# schema3.net
KiCad netlist of a schematic drawn in Altium Designer
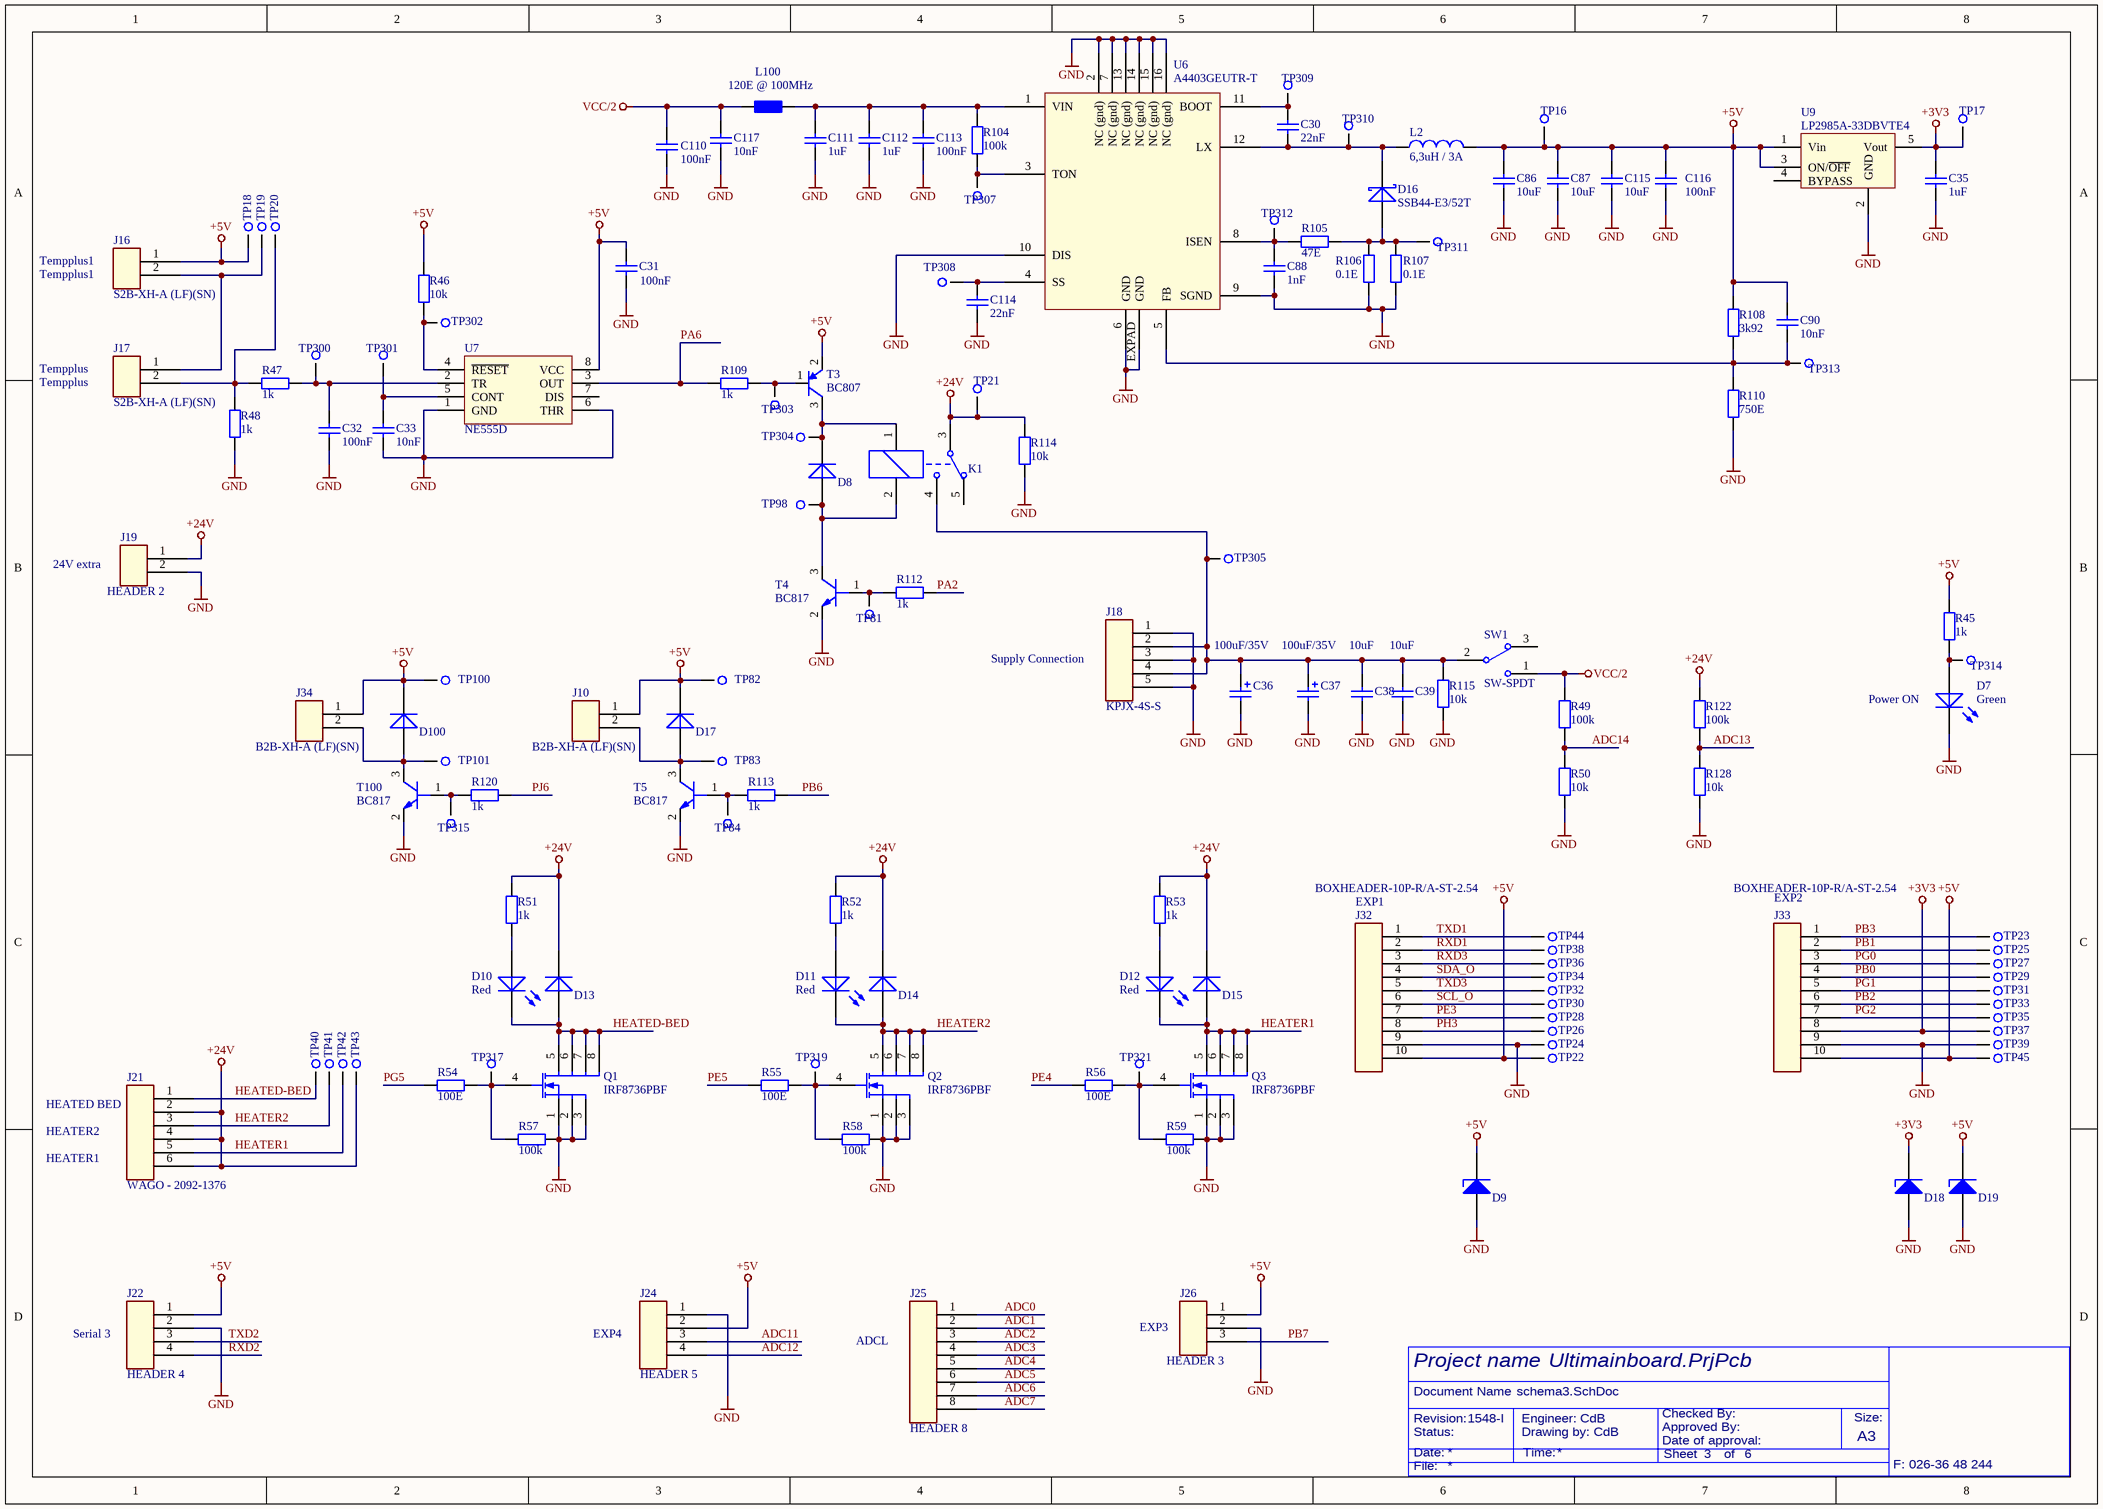
[diagram p0: schema3.SchDoc]

(export (version "E")
  (design (tool "Eeschema 10.0.6"))
  (components
    (comp (ref "C30")
      (value "22nF")
      (footprint "C0603")
      (description "RO X7R 22nF 10% 0603 50V CC0603KRX7R9BB223")
      (libsource (lib "Database_Faber") (part "Capacitor"))
    )
    (comp (ref "C31")
      (value "100nF")
      (footprint "C0603")
      (description "RO X7R 100nF 10% 50V 0603")
      (libsource (lib "Database_Faber") (part "Capacitor"))
    )
    (comp (ref "C32")
      (value "100nF")
      (footprint "C0603")
      (description "RO X7R 100nF 10% 50V 0603")
      (libsource (lib "Database_Faber") (part "Capacitor"))
    )
    (comp (ref "C33")
      (value "10nF")
      (footprint "C0603")
      (description "RO X7R 10nF 10% 50V 0603")
      (libsource (lib "Database_Faber") (part "Capacitor"))
    )
    (comp (ref "C35")
      (value "1uF")
      (footprint "C0603")
      (description "RO X5R 1uF 10% 10V 0603")
      (libsource (lib "Database_Faber") (part "Capacitor"))
    )
    (comp (ref "C36")
      (value "100uF/35V")
      (footprint "ELCO Case D")
      (description "RO ELCO 100uF 20% 35V CASE-D EEEFP PAN")
      (libsource (lib "Database_Faber") (part "Capacitor Polarity"))
    )
    (comp (ref "C37")
      (value "100uF/35V")
      (footprint "ELCO Case D")
      (description "RO ELCO 100uF 20% 35V CASE-D EEEFP PAN")
      (libsource (lib "Database_Faber") (part "Capacitor Polarity"))
    )
    (comp (ref "C38")
      (value "10uF")
      (footprint "C1206")
      (description "RO X5R 10UF 10% 35V 1206")
      (libsource (lib "Database_Faber") (part "Capacitor"))
    )
    (comp (ref "C39")
      (value "10uF")
      (footprint "C1206")
      (description "RO X5R 10UF 10% 35V 1206")
      (libsource (lib "Database_Faber") (part "Capacitor"))
    )
    (comp (ref "C86")
      (value "10uF")
      (footprint "C0805")
      (description "6R3R15X106KV4E - MLCC, 0805, X5R, 6.3V, 10UF")
      (fields (field (name "MFG") "JOHANSON DIELECTRICS"))
      (libsource (lib "Database_Faber") (part "Capacitor"))
    )
    (comp (ref "C87")
      (value "10uF")
      (footprint "C0805")
      (description "6R3R15X106KV4E - MLCC, 0805, X5R, 6.3V, 10UF")
      (fields (field (name "MFG") "JOHANSON DIELECTRICS"))
      (libsource (lib "Database_Faber") (part "Capacitor"))
    )
    (comp (ref "C88")
      (value "1nF")
      (footprint "C0603")
      (description "RO C0G 1nF 5% 50V 0603")
      (libsource (lib "Database_Faber") (part "Capacitor"))
    )
    (comp (ref "C90")
      (value "10nF")
      (footprint "C0603")
      (description "RO X7R 10nF 10% 50V 0603")
      (libsource (lib "Database_Faber") (part "Capacitor"))
    )
    (comp (ref "C110")
      (value "100nF")
      (footprint "Ultimaker:C0603")
      (description "RO X7R 100nF 10% 50V 0603")
      (libsource (lib "Database_Faber") (part "Capacitor"))
    )
    (comp (ref "C111")
      (value "1uF")
      (footprint "Ultimaker:C1206")
      (description "X7R 1uF 10% 50V 1206 GRM31")
      (libsource (lib "Ultimaker") (part "Capacitor_1_1"))
    )
    (comp (ref "C112")
      (value "1uF")
      (footprint "Ultimaker:C1206")
      (description "X7R 1uF 10% 50V 1206 GRM31")
      (libsource (lib "Ultimaker") (part "Capacitor_1_1"))
    )
    (comp (ref "C113")
      (value "100nF")
      (footprint "Ultimaker:C0603")
      (description "RO X7R 100nF 10% 50V 0603")
      (libsource (lib "Database_Faber") (part "Capacitor"))
    )
    (comp (ref "C114")
      (value "22nF")
      (footprint "Ultimaker:C0603")
      (description "RO X7R 22nF 10% 0603 50V CC0603KRX7R9BB223")
      (libsource (lib "Database_Faber") (part "Capacitor"))
    )
    (comp (ref "C115")
      (value "10uF")
      (footprint "Ultimaker:C0805")
      (description "6R3R15X106KV4E - MLCC, 0805, X5R, 6.3V, 10UF")
      (fields (field (name "MFG") "JOHANSON DIELECTRICS"))
      (libsource (lib "Database_Faber") (part "Capacitor"))
    )
    (comp (ref "C116")
      (value "100nF")
      (footprint "Ultimaker:C0603")
      (description "RO X7R 100nF 10% 50V 0603")
      (libsource (lib "Database_Faber") (part "Capacitor"))
    )
    (comp (ref "C117")
      (value "10nF")
      (footprint "Ultimaker:C0603")
      (description "RO X7R 10nF 10% 50V 0603")
      (libsource (lib "Database_Faber") (part "Capacitor"))
    )
    (comp (ref "D7")
      (value "Green")
      (footprint "LED0805-GREEN")
      (description "RO LED GROEN HSMG-C170 0805 AVAGO")
      (fields (field (name "MFG") "AVAGO"))
      (libsource (lib "Database_Faber") (part "LED"))
    )
    (comp (ref "D8")
      (value "S1G")
      (footprint "DO214AC (SMA)")
      (description "RO DIODE S1G DO-214AC")
      (libsource (lib "Database_Faber") (part "Diode"))
    )
    (comp (ref "D9")
      (value "ESD9X5.0ST5G")
      (footprint "SODFL100X40-2N")
      (description "TVS DIODE 5VWM 12.3VC SOD923")
      (fields (field (name "MFG") "ON Semiconductor"))
      (libsource (lib "Olimex interface board") (part "ESD9X5.0ST5G"))
    )
    (comp (ref "D10")
      (value "Red")
      (footprint "LED0805-RED")
      (description "RO LED ROOD HSMH-C170 0805 AVAGO")
      (fields (field (name "MFG") "AVAGO"))
      (libsource (lib "Database_Faber") (part "LED"))
    )
    (comp (ref "D11")
      (value "Red")
      (footprint "LED0805-RED")
      (description "RO LED ROOD HSMH-C170 0805 AVAGO")
      (fields (field (name "MFG") "AVAGO"))
      (libsource (lib "Database_Faber") (part "LED"))
    )
    (comp (ref "D12")
      (value "Red")
      (footprint "LED0805-RED")
      (description "RO LED ROOD HSMH-C170 0805 AVAGO")
      (fields (field (name "MFG") "AVAGO"))
      (libsource (lib "Database_Faber") (part "LED"))
    )
    (comp (ref "D13")
      (value "S1G")
      (footprint "DO214AC (SMA)")
      (description "RO DIODE S1G DO-214AC")
      (libsource (lib "Database_Faber") (part "Diode"))
    )
    (comp (ref "D14")
      (value "S1G")
      (footprint "DO214AC (SMA)")
      (description "RO DIODE S1G DO-214AC")
      (libsource (lib "Database_Faber") (part "Diode"))
    )
    (comp (ref "D15")
      (value "S1G")
      (footprint "DO214AC (SMA)")
      (description "RO DIODE S1G DO-214AC")
      (libsource (lib "Database_Faber") (part "Diode"))
    )
    (comp (ref "D16")
      (value "SSB44-E3/52T")
      (footprint "DO214AA (SMB)")
      (description "RO DIODE SSB44-E3/52T SMB VISHAY")
      (fields (field (name "MFG") "VISHAY"))
      (libsource (lib "Database_Faber") (part "Schottky"))
    )
    (comp (ref "D17")
      (value "S1G")
      (footprint "Ultimaker:DO214AC (SMA)")
      (description "RO DIODE S1G DO-214AC")
      (libsource (lib "") (part "Diode_1"))
    )
    (comp (ref "D18")
      (value "ESD9X3.3ST5G")
      (footprint "SODFL100X40-2N")
      (description "TVS DIODE 3.3VWM 10.4VC SOD923")
      (fields (field (name "MFG") "ON Semiconductor"))
      (libsource (lib "Olimex interface board") (part "ESD9X3.3ST5G"))
    )
    (comp (ref "D19")
      (value "ESD9X5.0ST5G")
      (footprint "SODFL100X40-2N")
      (description "TVS DIODE 5VWM 12.3VC SOD923")
      (fields (field (name "MFG") "ON Semiconductor"))
      (libsource (lib "Olimex interface board") (part "ESD9X5.0ST5G"))
    )
    (comp (ref "D100")
      (value "S1G")
      (footprint "Ultimaker:DO214AC (SMA)")
      (description "RO DIODE S1G DO-214AC")
      (libsource (lib "") (part "Diode_1"))
    )
    (comp (ref "J10")
      (value "B2B-XH-A (LF)(SN)")
      (footprint "B2B-XH-A (LF)(SN)")
      (description "CONN PR 2p B2B-XH-A JST")
      (fields (field (name "MFG") "JST (JAPAN SOLDERLESS TERMINALS)"))
      (libsource (lib "Ultimaker") (part "HEADER 2_3"))
    )
    (comp (ref "J16")
      (value "S2B-XH-A (LF)(SN)")
      (footprint "S2B-XH-A (LF)(SN)")
      (description "RO CONN PR 2p HKS S2B-XH-A (LF)(SN) JST")
      (fields (field (name "MFG") "JST (JAPAN SOLDERLESS TERMINALS)"))
      (libsource (lib "Database_Faber") (part "HEADER 2"))
    )
    (comp (ref "J17")
      (value "S2B-XH-A (LF)(SN)")
      (footprint "S2B-XH-A (LF)(SN)")
      (description "RO CONN PR 2p HKS S2B-XH-A (LF)(SN) JST")
      (fields (field (name "MFG") "JST (JAPAN SOLDERLESS TERMINALS)"))
      (libsource (lib "Database_Faber") (part "HEADER 2"))
    )
    (comp (ref "J18")
      (value "KPJX-4S-S")
      (footprint "KPJX-4S-S")
      (description "RO CONN PR KPJX-4S-S KYCON")
      (fields (field (name "MFG") "KYCON"))
      (libsource (lib "Database_Faber") (part "HEADER 5"))
    )
    (comp (ref "J19")
      (value "HEADER 2")
      (footprint "HEADER-1x2P-ST-2.54")
      (description "HEADER-1x2P-ST-2.54")
      (libsource (lib "Database_Faber") (part "HEADER 2"))
    )
    (comp (ref "J21")
      (value "WAGO - 2092-1376")
      (footprint "Wago connector:WAGO 2092-1376")
      (description "WAGO - 2092-1376 - TERMINAL BLOCK, PCB, R/A, 6WAY, 24-12AWG")
      (fields (field (name "MFG") "Wago"))
      (libsource (lib "Database_Faber") (part "HEADER 6"))
    )
    (comp (ref "J22")
      (value "HEADER 4")
      (footprint "HEADER-1x4P-ST-2.54")
      (description "HEADER-1x4P-ST-2.54")
      (libsource (lib "Database_Faber") (part "HEADER 4"))
    )
    (comp (ref "J24")
      (value "HEADER 5")
      (footprint "HEADER-1x4P-ST-2.54")
      (description "HEADER-1x4P-ST-2.54")
      (libsource (lib "Database_Faber") (part "HEADER 4"))
    )
    (comp (ref "J25")
      (value "HEADER 8")
      (footprint "HEADER-1x8P-ST-2.54")
      (description "HEADER-1x8P-ST-2.54")
      (libsource (lib "Database_Faber") (part "HEADER 8"))
    )
    (comp (ref "J26")
      (value "HEADER 3")
      (footprint "HEADER-1x3P-ST-2.54")
      (description "HEADER-1x3P-ST-2.54")
      (libsource (lib "Database_Faber") (part "HEADER 3"))
    )
    (comp (ref "J32")
      (value "BOXHEADER-10P-R/A-ST-2.54")
      (footprint "BOXHEADER-10P-R/A-ST-2.54")
      (description "RO CONN PR HDR BOX 10p HKS 61201021721 WUERTH")
      (libsource (lib "Database_Faber") (part "HEADER 10"))
    )
    (comp (ref "J33")
      (value "BOXHEADER-10P-R/A-ST-2.54")
      (footprint "BOXHEADER-10P-R/A-ST-2.54")
      (description "RO CONN PR HDR BOX 10p HKS 61201021721 WUERTH")
      (libsource (lib "Database_Faber") (part "HEADER 10"))
    )
    (comp (ref "J34")
      (value "B2B-XH-A (LF)(SN)")
      (footprint "B2B-XH-A (LF)(SN)")
      (description "CONN PR 2p B2B-XH-A JST")
      (fields (field (name "MFG") "JST (JAPAN SOLDERLESS TERMINALS)"))
      (libsource (lib "Ultimaker") (part "HEADER 2_3"))
    )
    (comp (ref "K1")
      (value "Relay-SPDT")
      (footprint "HRS4-S")
      (description "RO REL 5V HRS4-S DC5V MULTICOMP")
      (fields (field (name "MFG") "MULTICOMP"))
      (libsource (lib "Database_Faber") (part "Relay-SPDT"))
    )
    (comp (ref "L2")
      (value "6,3uH / 3A")
      (footprint "NRS6045")
      (description "RO SPOEL 6,3uH 20% NRS6045T 6R3MMGK TAIYO YUDEN")
      (fields (field (name "MFG") "TAIYO YUDEN"))
      (libsource (lib "Database_Faber") (part "Inductor"))
    )
    (comp (ref "L100")
      (value "120E @ 100MHz")
      (footprint "Ultimaker:R0603")
      (description "FERRIET BLM18PG121SN1D 0603 MURATA")
      (fields (field (name "MFG") "Murata"))
      (libsource (lib "Ultimaker") (part "Ferriet Bead 120E"))
    )
    (comp (ref "Q1")
      (value "IRF8736PBF")
      (footprint "SOIC127P600X175-8N (SO8)")
      (description "IRF8736PBF - MOSFET, N SO-8")
      (fields (field (name "MFG") "INTERNATIONAL RECTIFIER"))
      (libsource (lib "Database_Faber") (part "MOSFET-N-SO8"))
    )
    (comp (ref "Q2")
      (value "IRF8736PBF")
      (footprint "SOIC127P600X175-8N (SO8)")
      (description "IRF8736PBF - MOSFET, N SO-8")
      (fields (field (name "MFG") "INTERNATIONAL RECTIFIER"))
      (libsource (lib "Database_Faber") (part "MOSFET-N-SO8"))
    )
    (comp (ref "Q3")
      (value "IRF8736PBF")
      (footprint "SOIC127P600X175-8N (SO8)")
      (description "IRF8736PBF - MOSFET, N SO-8")
      (fields (field (name "MFG") "INTERNATIONAL RECTIFIER"))
      (libsource (lib "Database_Faber") (part "MOSFET-N-SO8"))
    )
    (comp (ref "R45")
      (value "1k")
      (footprint "R0603")
      (description "RO RES 1k0 1% 0,1W  0603")
      (libsource (lib "Database_Faber") (part "Resistor"))
    )
    (comp (ref "R46")
      (value "10k")
      (footprint "R0603")
      (description "RO RES 10k0 1% 0,063W  0603")
      (libsource (lib "Database_Faber") (part "Resistor"))
    )
    (comp (ref "R47")
      (value "1k")
      (footprint "R0603")
      (description "RO RES 1k0 1% 0,1W  0603")
      (libsource (lib "") (part "Resistor_1"))
    )
    (comp (ref "R48")
      (value "1k")
      (footprint "R0603")
      (description "RO RES 1k0 1% 0,1W  0603")
      (libsource (lib "Database_Faber") (part "Resistor"))
    )
    (comp (ref "R49")
      (value "100k")
      (footprint "R0603")
      (description "RO RES 100k0 1% 0,063W  0603")
      (libsource (lib "Database_Faber") (part "Resistor"))
    )
    (comp (ref "R50")
      (value "10k")
      (footprint "R0603")
      (description "RO RES 10k0 1% 0,063W  0603")
      (libsource (lib "Database_Faber") (part "Resistor"))
    )
    (comp (ref "R51")
      (value "1k")
      (footprint "R0603")
      (description "RO RES 1k0 1% 0,1W  0603")
      (libsource (lib "Database_Faber") (part "Resistor"))
    )
    (comp (ref "R52")
      (value "1k")
      (footprint "R0603")
      (description "RO RES 1k0 1% 0,1W  0603")
      (libsource (lib "Database_Faber") (part "Resistor"))
    )
    (comp (ref "R53")
      (value "1k")
      (footprint "R0603")
      (description "RO RES 1k0 1% 0,1W  0603")
      (libsource (lib "Database_Faber") (part "Resistor"))
    )
    (comp (ref "R54")
      (value "100E")
      (footprint "R0603")
      (description "RO RES 100E 1% 0,063W  0603")
      (libsource (lib "") (part "Resistor_1"))
    )
    (comp (ref "R55")
      (value "100E")
      (footprint "R0603")
      (description "RO RES 100E 1% 0,063W  0603")
      (libsource (lib "") (part "Resistor_1"))
    )
    (comp (ref "R56")
      (value "100E")
      (footprint "R0603")
      (description "RO RES 100E 1% 0,063W  0603")
      (libsource (lib "") (part "Resistor_1"))
    )
    (comp (ref "R57")
      (value "100k")
      (footprint "R0603")
      (description "RO RES 100k0 1% 0,063W  0603")
      (libsource (lib "") (part "Resistor_1"))
    )
    (comp (ref "R58")
      (value "100k")
      (footprint "R0603")
      (description "RO RES 100k0 1% 0,063W  0603")
      (libsource (lib "") (part "Resistor_1"))
    )
    (comp (ref "R59")
      (value "100k")
      (footprint "R0603")
      (description "RO RES 100k0 1% 0,063W  0603")
      (libsource (lib "") (part "Resistor_1"))
    )
    (comp (ref "R104")
      (value "100k")
      (footprint "R0603")
      (description "RO RES 100k0 1% 0,063W  0603")
      (libsource (lib "Database_Faber") (part "Resistor"))
    )
    (comp (ref "R105")
      (value "47E")
      (footprint "R0603")
      (description "RO RES 47E 1% 0,063W 0603")
      (libsource (lib "") (part "Resistor_1"))
    )
    (comp (ref "R106")
      (value "0.1E")
      (footprint "Ultimaker:R0805")
      (description "RES 0E10 1% 0,125W 0805")
      (libsource (lib "Database_Faber") (part "Resistor"))
    )
    (comp (ref "R107")
      (value "0.1E")
      (footprint "Ultimaker:R0805")
      (description "RES 0E10 1% 0,125W 0805")
      (libsource (lib "Database_Faber") (part "Resistor"))
    )
    (comp (ref "R108")
      (value "3k92")
      (footprint "R0603")
      (description "RO RES 3k92 1% 0.063W 0603")
      (libsource (lib "Database_Faber") (part "Resistor"))
    )
    (comp (ref "R109")
      (value "1k")
      (footprint "R0603")
      (description "RO RES 1k0 1% 0,1W  0603")
      (libsource (lib "") (part "Resistor_1"))
    )
    (comp (ref "R110")
      (value "750E")
      (footprint "R0603")
      (description "RO RES 750E 1% 0,063W 0603")
      (libsource (lib "Database_Faber") (part "Resistor"))
    )
    (comp (ref "R112")
      (value "1k")
      (footprint "Ultimaker:R0603")
      (description "RO RES 1k0 1% 0,1W  0603")
      (libsource (lib "") (part "Resistor_2"))
    )
    (comp (ref "R113")
      (value "1k")
      (footprint "Ultimaker:R0603")
      (description "RO RES 1k0 1% 0,1W  0603")
      (libsource (lib "") (part "Resistor_2"))
    )
    (comp (ref "R114")
      (value "10k")
      (footprint "R1206")
      (description "RO RES 10k0 1% 0,25W 1206")
      (fields (field (name "MFG") "Multicomp"))
      (libsource (lib "altium-import") (part "root_1_Resistor_"))
    )
    (comp (ref "R115")
      (value "10k")
      (footprint "R1206")
      (description "RO RES 10k0 1% 0,25W 1206")
      (fields (field (name "MFG") "Multicomp"))
      (libsource (lib "altium-import") (part "root_1_Resistor_"))
    )
    (comp (ref "R120")
      (value "1k")
      (footprint "Ultimaker:R0603")
      (description "RO RES 1k0 1% 0,1W  0603")
      (libsource (lib "") (part "Resistor_2"))
    )
    (comp (ref "R122")
      (value "100k")
      (footprint "R0603")
      (description "RO RES 100k0 1% 0,063W  0603")
      (libsource (lib "Database_Faber") (part "Resistor"))
    )
    (comp (ref "R128")
      (value "10k")
      (footprint "R0603")
      (description "RO RES 10k0 1% 0,063W  0603")
      (libsource (lib "Database_Faber") (part "Resistor"))
    )
    (comp (ref "SW1")
      (value "SW-SPDT")
      (footprint "RS 734-6918")
      (description "Rocker switch,SPDT,on-none-on,RA,snap-in")
      (fields (field (name "MFG") "Dailywell Electronics"))
      (libsource (lib "Database_Faber") (part "SW-SPDT"))
    )
    (comp (ref "T3")
      (value "BC807")
      (footprint "SOT23")
      (description "RO TRANS BC807-40  SOT-23")
      (libsource (lib "Database_Faber") (part "Transistor PNP"))
    )
    (comp (ref "T4")
      (value "BC817")
      (footprint "Ultimaker:SOT23")
      (description "RO TRANS BC817-25  SOT-23")
      (libsource (lib "Database_Faber") (part "Transistor NPN"))
    )
    (comp (ref "T5")
      (value "BC817")
      (footprint "Ultimaker:SOT23")
      (description "RO TRANS BC817-25  SOT-23")
      (libsource (lib "Database_Faber") (part "Transistor NPN"))
    )
    (comp (ref "T100")
      (value "BC817")
      (footprint "Ultimaker:SOT23")
      (description "RO TRANS BC817-25  SOT-23")
      (libsource (lib "Database_Faber") (part "Transistor NPN"))
    )
    (comp (ref "TP16")
      (value "Testpoint")
      (footprint "Testpoint")
      (libsource (lib "Database_Faber") (part "Testpoint"))
    )
    (comp (ref "TP17")
      (value "Testpoint")
      (footprint "Testpoint")
      (libsource (lib "Database_Faber") (part "Testpoint"))
    )
    (comp (ref "TP18")
      (value "Testpoint")
      (footprint "Testpoint")
      (libsource (lib "Database_Faber") (part "Testpoint"))
    )
    (comp (ref "TP19")
      (value "Testpoint")
      (footprint "Testpoint")
      (libsource (lib "Database_Faber") (part "Testpoint"))
    )
    (comp (ref "TP20")
      (value "Testpoint")
      (footprint "Testpoint")
      (libsource (lib "Database_Faber") (part "Testpoint"))
    )
    (comp (ref "TP21")
      (value "Testpoint")
      (footprint "Testpoint")
      (libsource (lib "Database_Faber") (part "Testpoint"))
    )
    (comp (ref "TP22")
      (value "Testpoint")
      (footprint "Testpoint")
      (libsource (lib "Database_Faber") (part "Testpoint"))
    )
    (comp (ref "TP23")
      (value "Testpoint")
      (footprint "Testpoint")
      (libsource (lib "Database_Faber") (part "Testpoint"))
    )
    (comp (ref "TP24")
      (value "Testpoint")
      (footprint "Testpoint")
      (libsource (lib "Database_Faber") (part "Testpoint"))
    )
    (comp (ref "TP25")
      (value "Testpoint")
      (footprint "Testpoint")
      (libsource (lib "Database_Faber") (part "Testpoint"))
    )
    (comp (ref "TP26")
      (value "Testpoint")
      (footprint "Testpoint")
      (libsource (lib "Database_Faber") (part "Testpoint"))
    )
    (comp (ref "TP27")
      (value "Testpoint")
      (footprint "Testpoint")
      (libsource (lib "Database_Faber") (part "Testpoint"))
    )
    (comp (ref "TP28")
      (value "Testpoint")
      (footprint "Testpoint")
      (libsource (lib "Database_Faber") (part "Testpoint"))
    )
    (comp (ref "TP29")
      (value "Testpoint")
      (footprint "Testpoint")
      (libsource (lib "Database_Faber") (part "Testpoint"))
    )
    (comp (ref "TP30")
      (value "Testpoint")
      (footprint "Testpoint")
      (libsource (lib "Database_Faber") (part "Testpoint"))
    )
    (comp (ref "TP31")
      (value "Testpoint")
      (footprint "Testpoint")
      (libsource (lib "Database_Faber") (part "Testpoint"))
    )
    (comp (ref "TP32")
      (value "Testpoint")
      (footprint "Testpoint")
      (libsource (lib "Database_Faber") (part "Testpoint"))
    )
    (comp (ref "TP33")
      (value "Testpoint")
      (footprint "Testpoint")
      (libsource (lib "Database_Faber") (part "Testpoint"))
    )
    (comp (ref "TP34")
      (value "Testpoint")
      (footprint "Testpoint")
      (libsource (lib "Database_Faber") (part "Testpoint"))
    )
    (comp (ref "TP35")
      (value "Testpoint")
      (footprint "Testpoint")
      (libsource (lib "Database_Faber") (part "Testpoint"))
    )
    (comp (ref "TP36")
      (value "Testpoint")
      (footprint "Testpoint")
      (libsource (lib "Database_Faber") (part "Testpoint"))
    )
    (comp (ref "TP37")
      (value "Testpoint")
      (footprint "Testpoint")
      (libsource (lib "Database_Faber") (part "Testpoint"))
    )
    (comp (ref "TP38")
      (value "Testpoint")
      (footprint "Testpoint")
      (libsource (lib "Database_Faber") (part "Testpoint"))
    )
    (comp (ref "TP39")
      (value "Testpoint")
      (footprint "Testpoint")
      (libsource (lib "Database_Faber") (part "Testpoint"))
    )
    (comp (ref "TP40")
      (value "Testpoint")
      (footprint "Testpoint")
      (libsource (lib "Database_Faber") (part "Testpoint"))
    )
    (comp (ref "TP41")
      (value "Testpoint")
      (footprint "Testpoint")
      (libsource (lib "Database_Faber") (part "Testpoint"))
    )
    (comp (ref "TP42")
      (value "Testpoint")
      (footprint "Testpoint")
      (libsource (lib "Database_Faber") (part "Testpoint"))
    )
    (comp (ref "TP43")
      (value "Testpoint")
      (footprint "Testpoint")
      (libsource (lib "Database_Faber") (part "Testpoint"))
    )
    (comp (ref "TP44")
      (value "Testpoint")
      (footprint "Testpoint")
      (libsource (lib "Database_Faber") (part "Testpoint"))
    )
    (comp (ref "TP45")
      (value "Testpoint")
      (footprint "Testpoint")
      (libsource (lib "Database_Faber") (part "Testpoint"))
    )
    (comp (ref "TP81")
      (value "Testpoint 1.6mm")
      (footprint "TESTPOINT")
      (libsource (lib "Ultimaker") (part "Testpoint 1.6mm"))
    )
    (comp (ref "TP82")
      (value "Testpoint")
      (footprint "Ultimaker:Testpoint")
      (libsource (lib "Database_Faber") (part "Testpoint"))
    )
    (comp (ref "TP83")
      (value "Testpoint")
      (footprint "Ultimaker:Testpoint")
      (libsource (lib "Database_Faber") (part "Testpoint"))
    )
    (comp (ref "TP84")
      (value "Testpoint 1.6mm")
      (footprint "Testpoint 1.6mm")
      (libsource (lib "Ultimaker") (part "Testpoint 1.6mm"))
    )
    (comp (ref "TP98")
      (value "Testpoint 1.6mm")
      (footprint "Testpoint 1.6mm")
      (libsource (lib "Ultimaker") (part "Testpoint 1.6mm"))
    )
    (comp (ref "TP100")
      (value "Testpoint")
      (footprint "Ultimaker:Testpoint")
      (libsource (lib "Database_Faber") (part "Testpoint"))
    )
    (comp (ref "TP101")
      (value "Testpoint")
      (footprint "Ultimaker:Testpoint")
      (libsource (lib "Database_Faber") (part "Testpoint"))
    )
    (comp (ref "TP300")
      (value "Testpoint 1.6mm")
      (footprint "Testpoint 1.6mm")
      (libsource (lib "Ultimaker") (part "Testpoint 1.6mm"))
    )
    (comp (ref "TP301")
      (value "Testpoint 1.6mm")
      (footprint "Testpoint 1.6mm")
      (libsource (lib "Ultimaker") (part "Testpoint 1.6mm"))
    )
    (comp (ref "TP302")
      (value "Testpoint 1.6mm")
      (footprint "Testpoint 1.6mm")
      (libsource (lib "Ultimaker") (part "Testpoint 1.6mm"))
    )
    (comp (ref "TP303")
      (value "Testpoint 1.6mm")
      (footprint "Testpoint 1.6mm")
      (libsource (lib "Ultimaker") (part "Testpoint 1.6mm"))
    )
    (comp (ref "TP304")
      (value "Testpoint 1.6mm")
      (footprint "Testpoint 1.6mm")
      (libsource (lib "Ultimaker") (part "Testpoint 1.6mm"))
    )
    (comp (ref "TP305")
      (value "Testpoint 1.6mm")
      (footprint "Testpoint 1.6mm")
      (libsource (lib "Ultimaker") (part "Testpoint 1.6mm"))
    )
    (comp (ref "TP307")
      (value "Testpoint 1.6mm")
      (footprint "Testpoint 1.6mm")
      (libsource (lib "Ultimaker") (part "Testpoint 1.6mm"))
    )
    (comp (ref "TP308")
      (value "Testpoint 1.6mm")
      (footprint "Testpoint 1.6mm")
      (libsource (lib "Ultimaker") (part "Testpoint 1.6mm"))
    )
    (comp (ref "TP309")
      (value "Testpoint 1.6mm")
      (footprint "Testpoint 1.6mm")
      (libsource (lib "Ultimaker") (part "Testpoint 1.6mm"))
    )
    (comp (ref "TP310")
      (value "Testpoint 1.6mm")
      (footprint "Testpoint 1.6mm")
      (libsource (lib "Ultimaker") (part "Testpoint 1.6mm"))
    )
    (comp (ref "TP311")
      (value "Testpoint 1.6mm")
      (footprint "Testpoint 1.6mm")
      (libsource (lib "Ultimaker") (part "Testpoint 1.6mm"))
    )
    (comp (ref "TP312")
      (value "Testpoint 1.6mm")
      (footprint "Testpoint 1.6mm")
      (libsource (lib "Ultimaker") (part "Testpoint 1.6mm"))
    )
    (comp (ref "TP313")
      (value "Testpoint 1.6mm")
      (footprint "Testpoint 1.6mm")
      (libsource (lib "Ultimaker") (part "Testpoint 1.6mm"))
    )
    (comp (ref "TP314")
      (value "Testpoint 1.6mm")
      (footprint "Testpoint 1.6mm")
      (libsource (lib "Ultimaker") (part "Testpoint 1.6mm"))
    )
    (comp (ref "TP315")
      (value "Testpoint 1.6mm")
      (footprint "Testpoint 1.6mm")
      (libsource (lib "Ultimaker") (part "Testpoint 1.6mm"))
    )
    (comp (ref "TP317")
      (value "Testpoint 1.6mm")
      (footprint "Testpoint 1.6mm")
      (libsource (lib "Ultimaker") (part "Testpoint 1.6mm"))
    )
    (comp (ref "TP319")
      (value "Testpoint 1.6mm")
      (footprint "Testpoint 1.6mm")
      (libsource (lib "Ultimaker") (part "Testpoint 1.6mm"))
    )
    (comp (ref "TP321")
      (value "Testpoint 1.6mm")
      (footprint "Testpoint 1.6mm")
      (libsource (lib "Ultimaker") (part "Testpoint 1.6mm"))
    )
    (comp (ref "U6")
      (value "A4403GEUTR-T")
      (footprint "QFN65P400X400X80-16N-EX")
      (description "RO IC A4403GEUTR-T QFN-16 ALLEGRO")
      (fields (field (name "MFG") "Allegro"))
      (libsource (lib "Database_Faber") (part "A4403GEUTR-T"))
    )
    (comp (ref "U7")
      (value "NE555D")
      (footprint "SOIC127P600X175-8N (SO8)")
      (description "RO IC NE555D SO-08 TI")
      (fields (field (name "MFG") "Texas Instruments"))
      (libsource (lib "Database_Faber") (part "NE555D"))
    )
    (comp (ref "U9")
      (value "LP2985A-33DBVTE4")
      (footprint "SOT95P280X145-5N (SOT23-5L)")
      (description "RO STABI LP2985A-33DBVTE4 SOT-23-5 TI")
      (fields (field (name "MFG") "Texas Instruments"))
      (libsource (lib "Database_Faber") (part "LP2985A-33DBVTE4"))
    )
  )
  (nets
    (net (code "1") (name "+3V3") (class "Default")
      (node (ref "C35") (pin "2") (pinfunction "2_2") (pintype "passive"))
      (node (ref "D18") (pin "1") (pinfunction "K_1") (pintype "passive"))
      (node (ref "J33") (pin "8") (pinfunction "8_8") (pintype "passive"))
      (node (ref "TP17") (pin "1") (pinfunction "1_1") (pintype "passive"))
      (node (ref "TP37") (pin "1") (pinfunction "1_1") (pintype "passive"))
      (node (ref "U9") (pin "5") (pinfunction "Vout_5") (pintype "passive"))
    )
    (net (code "2") (name "+5V") (class "Default")
      (node (ref "C115") (pin "2") (pinfunction "2_2") (pintype "passive"))
      (node (ref "C116") (pin "2") (pinfunction "2_2") (pintype "passive"))
      (node (ref "C31") (pin "2") (pinfunction "2_2") (pintype "passive"))
      (node (ref "C86") (pin "2") (pinfunction "2_2") (pintype "passive"))
      (node (ref "C87") (pin "2") (pinfunction "2_2") (pintype "passive"))
      (node (ref "C90") (pin "2") (pinfunction "2_2") (pintype "passive"))
      (node (ref "D100") (pin "2") (pinfunction "K_2") (pintype "passive"))
      (node (ref "D17") (pin "2") (pinfunction "K_2") (pintype "passive"))
      (node (ref "D19") (pin "1") (pinfunction "K_1") (pintype "passive"))
      (node (ref "D9") (pin "1") (pinfunction "K_1") (pintype "passive"))
      (node (ref "J10") (pin "1") (pinfunction "1_1") (pintype "passive"))
      (node (ref "J16") (pin "1") (pinfunction "1_1") (pintype "passive"))
      (node (ref "J22") (pin "1") (pinfunction "1_1") (pintype "passive"))
      (node (ref "J24") (pin "2") (pinfunction "2_2") (pintype "passive"))
      (node (ref "J26") (pin "1") (pinfunction "1_1") (pintype "passive"))
      (node (ref "J32") (pin "10") (pinfunction "10_10") (pintype "passive"))
      (node (ref "J33") (pin "10") (pinfunction "10_10") (pintype "passive"))
      (node (ref "J34") (pin "1") (pinfunction "1_1") (pintype "passive"))
      (node (ref "L2") (pin "2") (pinfunction "2_2") (pintype "passive"))
      (node (ref "R108") (pin "2") (pinfunction "2_2") (pintype "passive"))
      (node (ref "R45") (pin "2") (pinfunction "2_2") (pintype "passive"))
      (node (ref "R46") (pin "2") (pinfunction "2_2") (pintype "passive"))
      (node (ref "T3") (pin "2") (pinfunction "E_2") (pintype "passive"))
      (node (ref "TP100") (pin "1") (pinfunction "1_1") (pintype "passive"))
      (node (ref "TP16") (pin "1") (pinfunction "1_1") (pintype "passive"))
      (node (ref "TP18") (pin "1") (pinfunction "1_1") (pintype "passive"))
      (node (ref "TP22") (pin "1") (pinfunction "1_1") (pintype "passive"))
      (node (ref "TP45") (pin "1") (pinfunction "1_1") (pintype "passive"))
      (node (ref "TP82") (pin "1") (pinfunction "1_1") (pintype "passive"))
      (node (ref "U7") (pin "8") (pinfunction "VCC_8") (pintype "passive"))
      (node (ref "U9") (pin "1") (pinfunction "Vin_1") (pintype "passive"))
      (node (ref "U9") (pin "3") (pinfunction "ON/~{OFF}_3") (pintype "passive"))
    )
    (net (code "3") (name "+24V") (class "Default")
      (node (ref "D13") (pin "2") (pinfunction "K_2") (pintype "passive"))
      (node (ref "D14") (pin "2") (pinfunction "K_2") (pintype "passive"))
      (node (ref "D15") (pin "2") (pinfunction "K_2") (pintype "passive"))
      (node (ref "J19") (pin "1") (pinfunction "1_1") (pintype "passive"))
      (node (ref "J21") (pin "2") (pinfunction "2_2") (pintype "passive"))
      (node (ref "J21") (pin "4") (pinfunction "4_4") (pintype "passive"))
      (node (ref "J21") (pin "6") (pinfunction "6_6") (pintype "passive"))
      (node (ref "K1") (pin "3") (pinfunction "3_3") (pintype "passive"))
      (node (ref "R114") (pin "2") (pinfunction "2_2") (pintype "passive"))
      (node (ref "R122") (pin "2") (pinfunction "2_2") (pintype "passive"))
      (node (ref "R51") (pin "2") (pinfunction "2_2") (pintype "passive"))
      (node (ref "R52") (pin "2") (pinfunction "2_2") (pintype "passive"))
      (node (ref "R53") (pin "2") (pinfunction "2_2") (pintype "passive"))
      (node (ref "TP21") (pin "1") (pinfunction "1_1") (pintype "passive"))
      (node (ref "TP43") (pin "1") (pinfunction "1_1") (pintype "passive"))
    )
    (net (code "4") (name "/ADC0") (class "Default")
      (node (ref "J25") (pin "1") (pinfunction "1_1") (pintype "passive"))
    )
    (net (code "5") (name "/ADC1") (class "Default")
      (node (ref "J25") (pin "2") (pinfunction "2_2") (pintype "passive"))
    )
    (net (code "6") (name "/ADC2") (class "Default")
      (node (ref "J25") (pin "3") (pinfunction "3_3") (pintype "passive"))
    )
    (net (code "7") (name "/ADC3") (class "Default")
      (node (ref "J25") (pin "4") (pinfunction "4_4") (pintype "passive"))
    )
    (net (code "8") (name "/ADC4") (class "Default")
      (node (ref "J25") (pin "5") (pinfunction "5_5") (pintype "passive"))
    )
    (net (code "9") (name "/ADC5") (class "Default")
      (node (ref "J25") (pin "6") (pinfunction "6_6") (pintype "passive"))
    )
    (net (code "10") (name "/ADC6") (class "Default")
      (node (ref "J25") (pin "7") (pinfunction "7_7") (pintype "passive"))
    )
    (net (code "11") (name "/ADC7") (class "Default")
      (node (ref "J25") (pin "8") (pinfunction "8_8") (pintype "passive"))
    )
    (net (code "12") (name "/ADC11") (class "Default")
      (node (ref "J24") (pin "3") (pinfunction "3_3") (pintype "passive"))
    )
    (net (code "13") (name "/ADC12") (class "Default")
      (node (ref "J24") (pin "4") (pinfunction "4_4") (pintype "passive"))
    )
    (net (code "14") (name "/ADC13") (class "Default")
      (node (ref "R122") (pin "1") (pinfunction "1_1") (pintype "passive"))
      (node (ref "R128") (pin "2") (pinfunction "2_2") (pintype "passive"))
    )
    (net (code "15") (name "/ADC14") (class "Default")
      (node (ref "R49") (pin "1") (pinfunction "1_1") (pintype "passive"))
      (node (ref "R50") (pin "2") (pinfunction "2_2") (pintype "passive"))
    )
    (net (code "16") (name "/HEATED-BED") (class "Default")
      (node (ref "D10") (pin "2") (pinfunction "K_2") (pintype "passive"))
      (node (ref "D13") (pin "1") (pinfunction "A_1") (pintype "passive"))
      (node (ref "J21") (pin "1") (pinfunction "1_1") (pintype "passive"))
      (node (ref "Q1") (pin "5") (pinfunction "D_5") (pintype "passive"))
      (node (ref "Q1") (pin "6") (pinfunction "D_6") (pintype "passive"))
      (node (ref "Q1") (pin "7") (pinfunction "D_7") (pintype "passive"))
      (node (ref "Q1") (pin "8") (pinfunction "D_8") (pintype "passive"))
      (node (ref "TP40") (pin "1") (pinfunction "1_1") (pintype "passive"))
    )
    (net (code "17") (name "/HEATER1") (class "Default")
      (node (ref "D12") (pin "2") (pinfunction "K_2") (pintype "passive"))
      (node (ref "D15") (pin "1") (pinfunction "A_1") (pintype "passive"))
      (node (ref "J21") (pin "5") (pinfunction "5_5") (pintype "passive"))
      (node (ref "Q3") (pin "5") (pinfunction "D_5") (pintype "passive"))
      (node (ref "Q3") (pin "6") (pinfunction "D_6") (pintype "passive"))
      (node (ref "Q3") (pin "7") (pinfunction "D_7") (pintype "passive"))
      (node (ref "Q3") (pin "8") (pinfunction "D_8") (pintype "passive"))
      (node (ref "TP42") (pin "1") (pinfunction "1_1") (pintype "passive"))
    )
    (net (code "18") (name "/HEATER2") (class "Default")
      (node (ref "D11") (pin "2") (pinfunction "K_2") (pintype "passive"))
      (node (ref "D14") (pin "1") (pinfunction "A_1") (pintype "passive"))
      (node (ref "J21") (pin "3") (pinfunction "3_3") (pintype "passive"))
      (node (ref "Q2") (pin "5") (pinfunction "D_5") (pintype "passive"))
      (node (ref "Q2") (pin "6") (pinfunction "D_6") (pintype "passive"))
      (node (ref "Q2") (pin "7") (pinfunction "D_7") (pintype "passive"))
      (node (ref "Q2") (pin "8") (pinfunction "D_8") (pintype "passive"))
      (node (ref "TP41") (pin "1") (pinfunction "1_1") (pintype "passive"))
    )
    (net (code "19") (name "/PA2") (class "Default")
      (node (ref "R112") (pin "1") (pinfunction "1_1") (pintype "passive"))
    )
    (net (code "20") (name "/PA6") (class "Default")
      (node (ref "R109") (pin "1") (pinfunction "1_1") (pintype "passive"))
      (node (ref "U7") (pin "3") (pinfunction "OUT_3") (pintype "passive"))
    )
    (net (code "21") (name "/PB0") (class "Default")
      (node (ref "J33") (pin "4") (pinfunction "4_4") (pintype "passive"))
      (node (ref "TP29") (pin "1") (pinfunction "1_1") (pintype "passive"))
    )
    (net (code "22") (name "/PB1") (class "Default")
      (node (ref "J33") (pin "2") (pinfunction "2_2") (pintype "passive"))
      (node (ref "TP25") (pin "1") (pinfunction "1_1") (pintype "passive"))
    )
    (net (code "23") (name "/PB2") (class "Default")
      (node (ref "J33") (pin "6") (pinfunction "6_6") (pintype "passive"))
      (node (ref "TP33") (pin "1") (pinfunction "1_1") (pintype "passive"))
    )
    (net (code "24") (name "/PB3") (class "Default")
      (node (ref "J33") (pin "1") (pinfunction "1_1") (pintype "passive"))
      (node (ref "TP23") (pin "1") (pinfunction "1_1") (pintype "passive"))
    )
    (net (code "25") (name "/PB6") (class "Default")
      (node (ref "R113") (pin "1") (pinfunction "1_1") (pintype "passive"))
    )
    (net (code "26") (name "/PB7") (class "Default")
      (node (ref "J26") (pin "3") (pinfunction "3_3") (pintype "passive"))
    )
    (net (code "27") (name "/PE3") (class "Default")
      (node (ref "J32") (pin "7") (pinfunction "7_7") (pintype "passive"))
      (node (ref "TP28") (pin "1") (pinfunction "1_1") (pintype "passive"))
    )
    (net (code "28") (name "/PE4") (class "Default")
      (node (ref "R56") (pin "1") (pinfunction "1_1") (pintype "passive"))
    )
    (net (code "29") (name "/PE5") (class "Default")
      (node (ref "R55") (pin "1") (pinfunction "1_1") (pintype "passive"))
    )
    (net (code "30") (name "/PG0") (class "Default")
      (node (ref "J33") (pin "3") (pinfunction "3_3") (pintype "passive"))
      (node (ref "TP27") (pin "1") (pinfunction "1_1") (pintype "passive"))
    )
    (net (code "31") (name "/PG1") (class "Default")
      (node (ref "J33") (pin "5") (pinfunction "5_5") (pintype "passive"))
      (node (ref "TP31") (pin "1") (pinfunction "1_1") (pintype "passive"))
    )
    (net (code "32") (name "/PG2") (class "Default")
      (node (ref "J33") (pin "7") (pinfunction "7_7") (pintype "passive"))
      (node (ref "TP35") (pin "1") (pinfunction "1_1") (pintype "passive"))
    )
    (net (code "33") (name "/PG5") (class "Default")
      (node (ref "R54") (pin "1") (pinfunction "1_1") (pintype "passive"))
    )
    (net (code "34") (name "/PH3") (class "Default")
      (node (ref "J32") (pin "8") (pinfunction "8_8") (pintype "passive"))
      (node (ref "TP26") (pin "1") (pinfunction "1_1") (pintype "passive"))
    )
    (net (code "35") (name "/PJ6") (class "Default")
      (node (ref "R120") (pin "1") (pinfunction "1_1") (pintype "passive"))
    )
    (net (code "36") (name "/RXD1") (class "Default")
      (node (ref "J32") (pin "2") (pinfunction "2_2") (pintype "passive"))
      (node (ref "TP38") (pin "1") (pinfunction "1_1") (pintype "passive"))
    )
    (net (code "37") (name "/RXD2") (class "Default")
      (node (ref "J22") (pin "4") (pinfunction "4_4") (pintype "passive"))
    )
    (net (code "38") (name "/RXD3") (class "Default")
      (node (ref "J32") (pin "3") (pinfunction "3_3") (pintype "passive"))
      (node (ref "TP36") (pin "1") (pinfunction "1_1") (pintype "passive"))
    )
    (net (code "39") (name "/SCL_O") (class "Default")
      (node (ref "J32") (pin "6") (pinfunction "6_6") (pintype "passive"))
      (node (ref "TP30") (pin "1") (pinfunction "1_1") (pintype "passive"))
    )
    (net (code "40") (name "/SDA_O") (class "Default")
      (node (ref "J32") (pin "4") (pinfunction "4_4") (pintype "passive"))
      (node (ref "TP34") (pin "1") (pinfunction "1_1") (pintype "passive"))
    )
    (net (code "41") (name "/TXD1") (class "Default")
      (node (ref "J32") (pin "1") (pinfunction "1_1") (pintype "passive"))
      (node (ref "TP44") (pin "1") (pinfunction "1_1") (pintype "passive"))
    )
    (net (code "42") (name "/TXD2") (class "Default")
      (node (ref "J22") (pin "3") (pinfunction "3_3") (pintype "passive"))
    )
    (net (code "43") (name "/TXD3") (class "Default")
      (node (ref "J32") (pin "5") (pinfunction "5_5") (pintype "passive"))
      (node (ref "TP32") (pin "1") (pinfunction "1_1") (pintype "passive"))
    )
    (net (code "44") (name "GND") (class "Default")
      (node (ref "C110") (pin "1") (pinfunction "1_1") (pintype "passive"))
      (node (ref "C111") (pin "1") (pinfunction "1_1") (pintype "passive"))
      (node (ref "C112") (pin "1") (pinfunction "1_1") (pintype "passive"))
      (node (ref "C113") (pin "1") (pinfunction "1_1") (pintype "passive"))
      (node (ref "C114") (pin "1") (pinfunction "1_1") (pintype "passive"))
      (node (ref "C115") (pin "1") (pinfunction "1_1") (pintype "passive"))
      (node (ref "C116") (pin "1") (pinfunction "1_1") (pintype "passive"))
      (node (ref "C117") (pin "1") (pinfunction "1_1") (pintype "passive"))
      (node (ref "C31") (pin "1") (pinfunction "1_1") (pintype "passive"))
      (node (ref "C32") (pin "1") (pinfunction "1_1") (pintype "passive"))
      (node (ref "C33") (pin "1") (pinfunction "1_1") (pintype "passive"))
      (node (ref "C35") (pin "1") (pinfunction "1_1") (pintype "passive"))
      (node (ref "C36") (pin "2") (pinfunction "2_2") (pintype "passive"))
      (node (ref "C37") (pin "2") (pinfunction "2_2") (pintype "passive"))
      (node (ref "C38") (pin "1") (pinfunction "1_1") (pintype "passive"))
      (node (ref "C39") (pin "1") (pinfunction "1_1") (pintype "passive"))
      (node (ref "C86") (pin "1") (pinfunction "1_1") (pintype "passive"))
      (node (ref "C87") (pin "1") (pinfunction "1_1") (pintype "passive"))
      (node (ref "C88") (pin "1") (pinfunction "1_1") (pintype "passive"))
      (node (ref "D18") (pin "2") (pinfunction "A_2") (pintype "passive"))
      (node (ref "D19") (pin "2") (pinfunction "A_2") (pintype "passive"))
      (node (ref "D7") (pin "2") (pinfunction "K_2") (pintype "passive"))
      (node (ref "D9") (pin "2") (pinfunction "A_2") (pintype "passive"))
      (node (ref "J18") (pin "1") (pinfunction "1_1") (pintype "passive"))
      (node (ref "J18") (pin "3") (pinfunction "3_3") (pintype "passive"))
      (node (ref "J18") (pin "5") (pinfunction "5_5") (pintype "passive"))
      (node (ref "J19") (pin "2") (pinfunction "2_2") (pintype "passive"))
      (node (ref "J22") (pin "2") (pinfunction "2_2") (pintype "passive"))
      (node (ref "J24") (pin "1") (pinfunction "1_1") (pintype "passive"))
      (node (ref "J26") (pin "2") (pinfunction "2_2") (pintype "passive"))
      (node (ref "J32") (pin "9") (pinfunction "9_9") (pintype "passive"))
      (node (ref "J33") (pin "9") (pinfunction "9_9") (pintype "passive"))
      (node (ref "Q1") (pin "1") (pinfunction "S_1") (pintype "passive"))
      (node (ref "Q1") (pin "2") (pinfunction "S_2") (pintype "passive"))
      (node (ref "Q1") (pin "3") (pinfunction "S_3") (pintype "passive"))
      (node (ref "Q2") (pin "1") (pinfunction "S_1") (pintype "passive"))
      (node (ref "Q2") (pin "2") (pinfunction "S_2") (pintype "passive"))
      (node (ref "Q2") (pin "3") (pinfunction "S_3") (pintype "passive"))
      (node (ref "Q3") (pin "1") (pinfunction "S_1") (pintype "passive"))
      (node (ref "Q3") (pin "2") (pinfunction "S_2") (pintype "passive"))
      (node (ref "Q3") (pin "3") (pinfunction "S_3") (pintype "passive"))
      (node (ref "R106") (pin "1") (pinfunction "1_1") (pintype "passive"))
      (node (ref "R107") (pin "1") (pinfunction "1_1") (pintype "passive"))
      (node (ref "R110") (pin "1") (pinfunction "1_1") (pintype "passive"))
      (node (ref "R114") (pin "1") (pinfunction "1_1") (pintype "passive"))
      (node (ref "R115") (pin "1") (pinfunction "1_1") (pintype "passive"))
      (node (ref "R128") (pin "1") (pinfunction "1_1") (pintype "passive"))
      (node (ref "R48") (pin "1") (pinfunction "1_1") (pintype "passive"))
      (node (ref "R50") (pin "1") (pinfunction "1_1") (pintype "passive"))
      (node (ref "R57") (pin "2") (pinfunction "2_2") (pintype "passive"))
      (node (ref "R58") (pin "2") (pinfunction "2_2") (pintype "passive"))
      (node (ref "R59") (pin "2") (pinfunction "2_2") (pintype "passive"))
      (node (ref "T100") (pin "2") (pinfunction "EMITTER_2") (pintype "passive"))
      (node (ref "T4") (pin "2") (pinfunction "EMITTER_2") (pintype "passive"))
      (node (ref "T5") (pin "2") (pinfunction "EMITTER_2") (pintype "passive"))
      (node (ref "TP24") (pin "1") (pinfunction "1_1") (pintype "passive"))
      (node (ref "TP39") (pin "1") (pinfunction "1_1") (pintype "passive"))
      (node (ref "U6") (pin "10") (pinfunction "DIS_10") (pintype "passive"))
      (node (ref "U6") (pin "13") (pinfunction "NC_(gnd)_13") (pintype "passive"))
      (node (ref "U6") (pin "14") (pinfunction "NC_(gnd)_14") (pintype "passive"))
      (node (ref "U6") (pin "15") (pinfunction "NC_(gnd)_15") (pintype "passive"))
      (node (ref "U6") (pin "16") (pinfunction "NC_(gnd)_16") (pintype "passive"))
      (node (ref "U6") (pin "2") (pinfunction "NC_(gnd)_2") (pintype "passive"))
      (node (ref "U6") (pin "6") (pinfunction "GND_6") (pintype "passive"))
      (node (ref "U6") (pin "7") (pinfunction "NC_(gnd)_7") (pintype "passive"))
      (node (ref "U6") (pin "9") (pinfunction "SGND_9") (pintype "passive"))
      (node (ref "U6") (pin "EXPAD") (pinfunction "GND_EXPAD") (pintype "passive"))
      (node (ref "U7") (pin "1") (pinfunction "GND_1") (pintype "passive"))
      (node (ref "U7") (pin "6") (pinfunction "THR_6") (pintype "passive"))
      (node (ref "U9") (pin "2") (pinfunction "GND_2") (pintype "passive"))
    )
    (net (code "45") (name "Net-(C36-Pad1)") (class "Default")
      (node (ref "C36") (pin "1") (pinfunction "1_1") (pintype "passive"))
      (node (ref "C37") (pin "1") (pinfunction "1_1") (pintype "passive"))
      (node (ref "C38") (pin "2") (pinfunction "2_2") (pintype "passive"))
      (node (ref "C39") (pin "2") (pinfunction "2_2") (pintype "passive"))
      (node (ref "J18") (pin "2") (pinfunction "2_2") (pintype "passive"))
      (node (ref "J18") (pin "4") (pinfunction "4_4") (pintype "passive"))
      (node (ref "K1") (pin "4") (pinfunction "4_4") (pintype "passive"))
      (node (ref "R115") (pin "2") (pinfunction "2_2") (pintype "passive"))
      (node (ref "SW1") (pin "2") (pinfunction "2_2") (pintype "passive"))
      (node (ref "TP305") (pin "1") (pinfunction "1_1") (pintype "passive"))
    )
    (net (code "46") (name "Net-(D7-A)") (class "Default")
      (node (ref "D7") (pin "1") (pinfunction "A_1") (pintype "passive"))
      (node (ref "R45") (pin "1") (pinfunction "1_1") (pintype "passive"))
      (node (ref "TP314") (pin "1") (pinfunction "1_1") (pintype "passive"))
    )
    (net (code "47") (name "Net-(D8-A)") (class "Default")
      (node (ref "D8") (pin "1") (pinfunction "A_1") (pintype "passive"))
      (node (ref "K1") (pin "2") (pinfunction "2_2") (pintype "passive"))
      (node (ref "T4") (pin "3") (pinfunction "COLLECTOR_3") (pintype "passive"))
      (node (ref "TP98") (pin "1") (pinfunction "1_1") (pintype "passive"))
    )
    (net (code "48") (name "Net-(D8-K)") (class "Default")
      (node (ref "D8") (pin "2") (pinfunction "K_2") (pintype "passive"))
      (node (ref "K1") (pin "1") (pinfunction "1_1") (pintype "passive"))
      (node (ref "T3") (pin "3") (pinfunction "C_3") (pintype "passive"))
      (node (ref "TP304") (pin "1") (pinfunction "1_1") (pintype "passive"))
    )
    (net (code "49") (name "Net-(D10-A)") (class "Default")
      (node (ref "D10") (pin "1") (pinfunction "A_1") (pintype "passive"))
      (node (ref "R51") (pin "1") (pinfunction "1_1") (pintype "passive"))
    )
    (net (code "50") (name "Net-(D11-A)") (class "Default")
      (node (ref "D11") (pin "1") (pinfunction "A_1") (pintype "passive"))
      (node (ref "R52") (pin "1") (pinfunction "1_1") (pintype "passive"))
    )
    (net (code "51") (name "Net-(D12-A)") (class "Default")
      (node (ref "D12") (pin "1") (pinfunction "A_1") (pintype "passive"))
      (node (ref "R53") (pin "1") (pinfunction "1_1") (pintype "passive"))
    )
    (net (code "52") (name "Net-(D16-A)") (class "Default")
      (node (ref "D16") (pin "1") (pinfunction "A_1") (pintype "passive"))
      (node (ref "R105") (pin "2") (pinfunction "2_2") (pintype "passive"))
      (node (ref "R106") (pin "2") (pinfunction "2_2") (pintype "passive"))
      (node (ref "R107") (pin "2") (pinfunction "2_2") (pintype "passive"))
      (node (ref "TP311") (pin "1") (pinfunction "1_1") (pintype "passive"))
    )
    (net (code "53") (name "Net-(D16-K)") (class "Default")
      (node (ref "C30") (pin "1") (pinfunction "1_1") (pintype "passive"))
      (node (ref "D16") (pin "2") (pinfunction "K_2") (pintype "passive"))
      (node (ref "L2") (pin "1") (pinfunction "1_1") (pintype "passive"))
      (node (ref "TP310") (pin "1") (pinfunction "1_1") (pintype "passive"))
      (node (ref "U6") (pin "12") (pinfunction "LX_12") (pintype "passive"))
    )
    (net (code "54") (name "Net-(D17-A)") (class "Default")
      (node (ref "D17") (pin "1") (pinfunction "A_1") (pintype "passive"))
      (node (ref "J10") (pin "2") (pinfunction "2_2") (pintype "passive"))
      (node (ref "T5") (pin "3") (pinfunction "COLLECTOR_3") (pintype "passive"))
      (node (ref "TP83") (pin "1") (pinfunction "1_1") (pintype "passive"))
    )
    (net (code "55") (name "Net-(D100-A)") (class "Default")
      (node (ref "D100") (pin "1") (pinfunction "A_1") (pintype "passive"))
      (node (ref "J34") (pin "2") (pinfunction "2_2") (pintype "passive"))
      (node (ref "T100") (pin "3") (pinfunction "COLLECTOR_3") (pintype "passive"))
      (node (ref "TP101") (pin "1") (pinfunction "1_1") (pintype "passive"))
    )
    (net (code "56") (name "Net-(J16-Pad2)") (class "Default")
      (node (ref "J16") (pin "2") (pinfunction "2_2") (pintype "passive"))
      (node (ref "J17") (pin "1") (pinfunction "1_1") (pintype "passive"))
      (node (ref "TP19") (pin "1") (pinfunction "1_1") (pintype "passive"))
    )
    (net (code "57") (name "Net-(J17-Pad2)") (class "Default")
      (node (ref "J17") (pin "2") (pinfunction "2_2") (pintype "passive"))
      (node (ref "R47") (pin "1") (pinfunction "1_1") (pintype "passive"))
      (node (ref "R48") (pin "2") (pinfunction "2_2") (pintype "passive"))
      (node (ref "TP20") (pin "1") (pinfunction "1_1") (pintype "passive"))
    )
    (net (code "58") (name "Net-(Q1-G)") (class "Default")
      (node (ref "Q1") (pin "4") (pinfunction "G_4") (pintype "passive"))
      (node (ref "R54") (pin "2") (pinfunction "2_2") (pintype "passive"))
      (node (ref "R57") (pin "1") (pinfunction "1_1") (pintype "passive"))
      (node (ref "TP317") (pin "1") (pinfunction "1_1") (pintype "passive"))
    )
    (net (code "59") (name "Net-(Q2-G)") (class "Default")
      (node (ref "Q2") (pin "4") (pinfunction "G_4") (pintype "passive"))
      (node (ref "R55") (pin "2") (pinfunction "2_2") (pintype "passive"))
      (node (ref "R58") (pin "1") (pinfunction "1_1") (pintype "passive"))
      (node (ref "TP319") (pin "1") (pinfunction "1_1") (pintype "passive"))
    )
    (net (code "60") (name "Net-(Q3-G)") (class "Default")
      (node (ref "Q3") (pin "4") (pinfunction "G_4") (pintype "passive"))
      (node (ref "R56") (pin "2") (pinfunction "2_2") (pintype "passive"))
      (node (ref "R59") (pin "1") (pinfunction "1_1") (pintype "passive"))
      (node (ref "TP321") (pin "1") (pinfunction "1_1") (pintype "passive"))
    )
    (net (code "61") (name "Net-(T3-B)") (class "Default")
      (node (ref "R109") (pin "2") (pinfunction "2_2") (pintype "passive"))
      (node (ref "T3") (pin "1") (pinfunction "B_1") (pintype "passive"))
      (node (ref "TP303") (pin "1") (pinfunction "1_1") (pintype "passive"))
    )
    (net (code "62") (name "Net-(T4-BASE)") (class "Default")
      (node (ref "R112") (pin "2") (pinfunction "2_2") (pintype "passive"))
      (node (ref "T4") (pin "1") (pinfunction "BASE_1") (pintype "passive"))
      (node (ref "TP81") (pin "1") (pinfunction "1_1") (pintype "passive"))
    )
    (net (code "63") (name "Net-(T5-BASE)") (class "Default")
      (node (ref "R113") (pin "2") (pinfunction "2_2") (pintype "passive"))
      (node (ref "T5") (pin "1") (pinfunction "BASE_1") (pintype "passive"))
      (node (ref "TP84") (pin "1") (pinfunction "1_1") (pintype "passive"))
    )
    (net (code "64") (name "Net-(T100-BASE)") (class "Default")
      (node (ref "R120") (pin "2") (pinfunction "2_2") (pintype "passive"))
      (node (ref "T100") (pin "1") (pinfunction "BASE_1") (pintype "passive"))
      (node (ref "TP315") (pin "1") (pinfunction "1_1") (pintype "passive"))
    )
    (net (code "65") (name "Net-(U6-BOOT)") (class "Default")
      (node (ref "C30") (pin "2") (pinfunction "2_2") (pintype "passive"))
      (node (ref "TP309") (pin "1") (pinfunction "1_1") (pintype "passive"))
      (node (ref "U6") (pin "11") (pinfunction "BOOT_11") (pintype "passive"))
    )
    (net (code "66") (name "Net-(U6-FB)") (class "Default")
      (node (ref "C90") (pin "1") (pinfunction "1_1") (pintype "passive"))
      (node (ref "R108") (pin "1") (pinfunction "1_1") (pintype "passive"))
      (node (ref "R110") (pin "2") (pinfunction "2_2") (pintype "passive"))
      (node (ref "TP313") (pin "1") (pinfunction "1_1") (pintype "passive"))
      (node (ref "U6") (pin "5") (pinfunction "FB_5") (pintype "passive"))
    )
    (net (code "67") (name "Net-(U6-ISEN)") (class "Default")
      (node (ref "C88") (pin "2") (pinfunction "2_2") (pintype "passive"))
      (node (ref "R105") (pin "1") (pinfunction "1_1") (pintype "passive"))
      (node (ref "TP312") (pin "1") (pinfunction "1_1") (pintype "passive"))
      (node (ref "U6") (pin "8") (pinfunction "ISEN_8") (pintype "passive"))
    )
    (net (code "68") (name "Net-(U6-SS)") (class "Default")
      (node (ref "C114") (pin "2") (pinfunction "2_2") (pintype "passive"))
      (node (ref "TP308") (pin "1") (pinfunction "1_1") (pintype "passive"))
      (node (ref "U6") (pin "4") (pinfunction "SS_4") (pintype "passive"))
    )
    (net (code "69") (name "Net-(U6-TON)") (class "Default")
      (node (ref "R104") (pin "1") (pinfunction "1_1") (pintype "passive"))
      (node (ref "TP307") (pin "1") (pinfunction "1_1") (pintype "passive"))
      (node (ref "U6") (pin "3") (pinfunction "TON_3") (pintype "passive"))
    )
    (net (code "70") (name "Net-(U6-VIN)") (class "Default")
      (node (ref "C111") (pin "2") (pinfunction "2_2") (pintype "passive"))
      (node (ref "C112") (pin "2") (pinfunction "2_2") (pintype "passive"))
      (node (ref "C113") (pin "2") (pinfunction "2_2") (pintype "passive"))
      (node (ref "L100") (pin "2") (pinfunction "2_2") (pintype "passive"))
      (node (ref "R104") (pin "2") (pinfunction "2_2") (pintype "passive"))
      (node (ref "U6") (pin "1") (pinfunction "VIN_1") (pintype "passive"))
    )
    (net (code "71") (name "Net-(U7-CONT)") (class "Default")
      (node (ref "C33") (pin "2") (pinfunction "2_2") (pintype "passive"))
      (node (ref "TP301") (pin "1") (pinfunction "1_1") (pintype "passive"))
      (node (ref "U7") (pin "5") (pinfunction "CONT_5") (pintype "passive"))
    )
    (net (code "72") (name "Net-(U7-TR)") (class "Default")
      (node (ref "C32") (pin "2") (pinfunction "2_2") (pintype "passive"))
      (node (ref "R47") (pin "2") (pinfunction "2_2") (pintype "passive"))
      (node (ref "TP300") (pin "1") (pinfunction "1_1") (pintype "passive"))
      (node (ref "U7") (pin "2") (pinfunction "TR_2") (pintype "passive"))
    )
    (net (code "73") (name "Net-(U7-~{RESET})") (class "Default")
      (node (ref "R46") (pin "1") (pinfunction "1_1") (pintype "passive"))
      (node (ref "TP302") (pin "1") (pinfunction "1_1") (pintype "passive"))
      (node (ref "U7") (pin "4") (pinfunction "~{RESET}_4") (pintype "passive"))
    )
    (net (code "74") (name "VCC{slash}2") (class "Default")
      (node (ref "C110") (pin "2") (pinfunction "2_2") (pintype "passive"))
      (node (ref "C117") (pin "2") (pinfunction "2_2") (pintype "passive"))
      (node (ref "L100") (pin "1") (pinfunction "1_1") (pintype "passive"))
      (node (ref "R49") (pin "2") (pinfunction "2_2") (pintype "passive"))
      (node (ref "SW1") (pin "1") (pinfunction "1_1") (pintype "passive"))
    )
    (net (code "75") (name "unconnected-(K1-Pad5)") (class "Default")
      (node (ref "K1") (pin "5") (pinfunction "5_5") (pintype "passive"))
    )
    (net (code "76") (name "unconnected-(SW1-Pad3)") (class "Default")
      (node (ref "SW1") (pin "3") (pinfunction "3_3") (pintype "passive"))
    )
    (net (code "77") (name "unconnected-(U7-DIS-Pad7)") (class "Default")
      (node (ref "U7") (pin "7") (pinfunction "DIS_7") (pintype "passive"))
    )
    (net (code "78") (name "unconnected-(U9-BYPASS-Pad4)") (class "Default")
      (node (ref "U9") (pin "4") (pinfunction "BYPASS_4") (pintype "passive"))
    )
  )
)
